# battery-module-60mm-side.net
KiCad netlist of a schematic drawn in Altium Designer
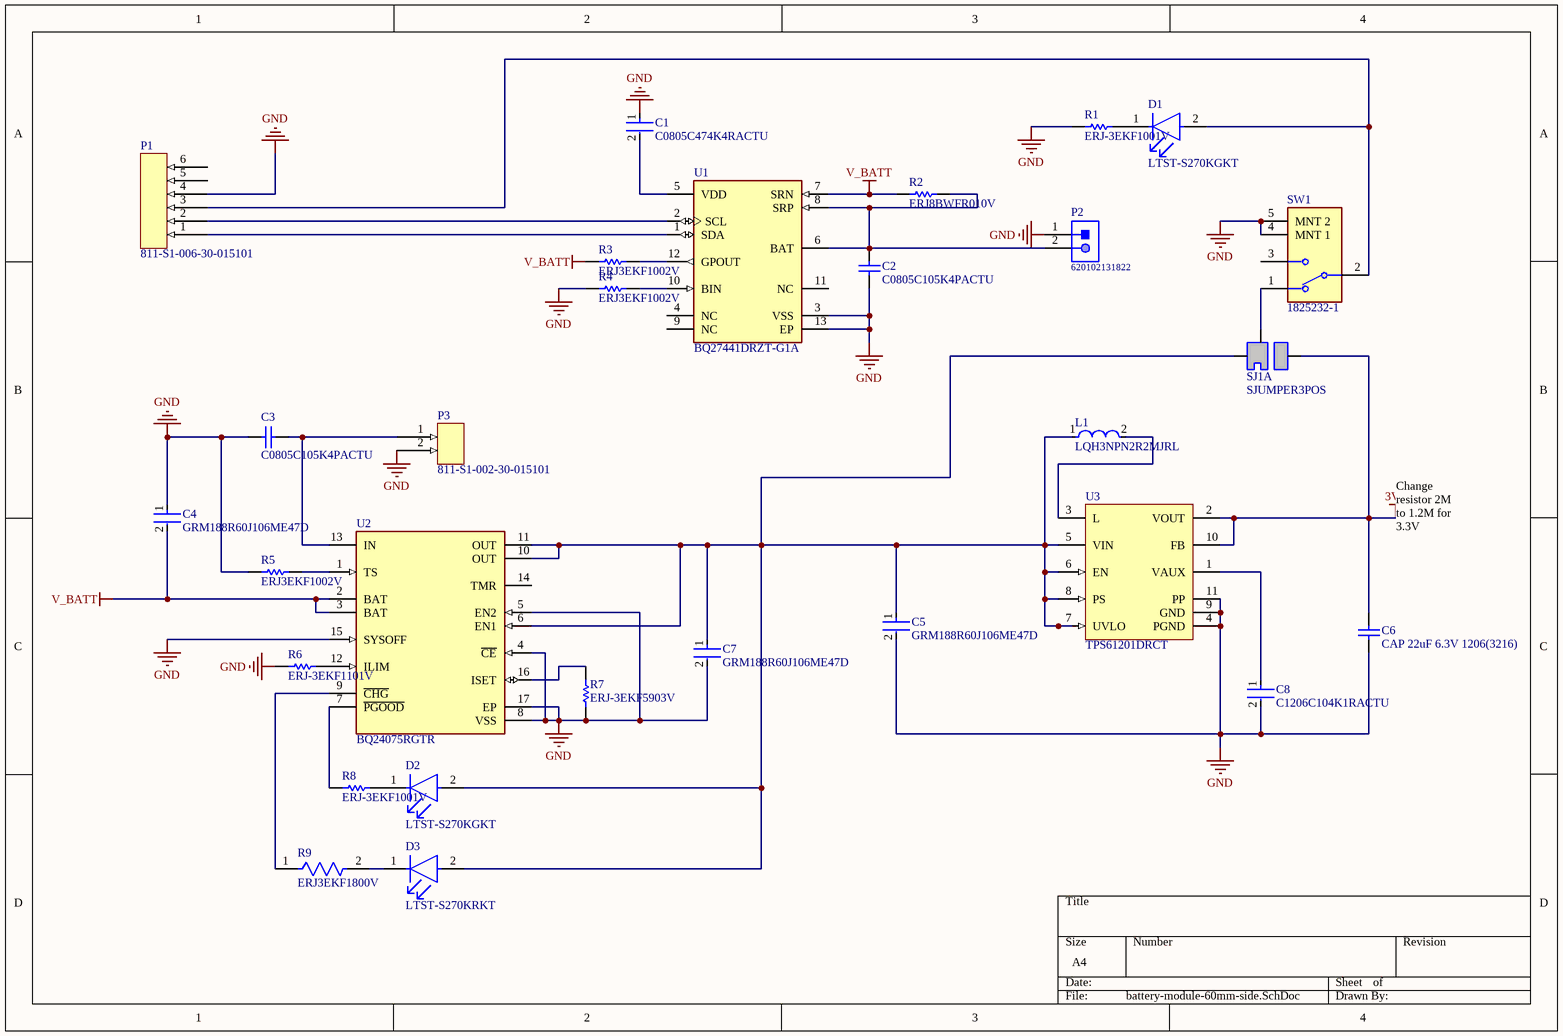
[diagram p0: battery-module-60mm-side.SchDoc]

(export (version "E")
  (design (tool "Eeschema 10.0.6"))
  (components
    (comp (ref "C1")
      (value "C0805C474K4RACTU")
      (footprint "FP-C0805C-DN-MFG")
      (description "CAP CER 0.47UF 16V 10% X7R 0805")
      (fields
        (field (name "OCTOPART") "https://octopart.com/c0805c474k4ractu-kemet-107561")
        (field (name "MANUFACTURER") "KEMET")
      )
      (libsource (lib "Altium Content Vault") (part "b4654b650e69147ec39a6b967a45e02"))
    )
    (comp (ref "C2")
      (value "C0805C105K4PACTU")
      (footprint "CAPC2013X145X50ML20T25")
      (fields (field (name "MANUFACTURER") "Kemet"))
      (libsource (lib "Altium Content Vault") (part "CAP"))
    )
    (comp (ref "C3")
      (value "C0805C105K4PACTU")
      (footprint "CAPC2013X145X50ML20T25")
      (fields (field (name "MANUFACTURER") "Kemet"))
      (libsource (lib "Altium Content Vault") (part "CAP"))
    )
    (comp (ref "C4")
      (value "GRM188R60J106ME47D")
      (footprint "FP-GRM188-0_1-e0_2_0_55-IPC_A")
      (description "Chip Multilayer Ceramic Capacitors for General Purpose, 0603, 10uF, X5R, 15%, 20%, 6.3V")
      (fields (field (name "VOLTAGE") "6.3V") (field (name "TOLERANCE") "20%"))
      (libsource (lib "Altium Content Vault") (part "02cd4be3c70576c341d710602a673aa"))
    )
    (comp (ref "C5")
      (value "GRM188R60J106ME47D")
      (footprint "FP-GRM188-0_1-e0_2_0_55-IPC_A")
      (description "Chip Multilayer Ceramic Capacitors for General Purpose, 0603, 10uF, X5R, 15%, 20%, 6.3V")
      (fields (field (name "VOLTAGE") "6.3V") (field (name "TOLERANCE") "20%"))
      (libsource (lib "Altium Content Vault") (part "02cd4be3c70576c341d710602a673aa"))
    )
    (comp (ref "C6")
      (value "CAP 22uF 6.3V 1206(3216)")
      (footprint "CAPC1206(3216)190_L")
      (description "CAP 22uF 6.3V ±20% 1206 (3216 Metric) Thickness 1.9mm SMD")
      (fields (field (name "TOLERANCE") "Â±20%"))
      (libsource (lib "Altium Content Vault") (part "CAP"))
    )
    (comp (ref "C7")
      (value "GRM188R60J106ME47D")
      (footprint "FP-GRM188-0_1-e0_2_0_55-IPC_A")
      (description "Chip Multilayer Ceramic Capacitors for General Purpose, 0603, 10uF, X5R, 15%, 20%, 6.3V")
      (fields (field (name "VOLTAGE") "6.3V") (field (name "TOLERANCE") "20%"))
      (libsource (lib "Altium Content Vault") (part "02cd4be3c70576c341d710602a673aa"))
    )
    (comp (ref "C8")
      (value "C1206C104K1RACTU")
      (footprint "FP-C1206C-EB-MFG")
      (description "CAP CER 0.1UF 100V X7R 1206")
      (fields
        (field (name "TOLERANCE") "0.1")
        (field (name "OCTOPART") "https://octopart.com/c1206c104k1ractu-kemet-89521")
      )
      (libsource (lib "Altium Content Vault") (part "b4654b650e69147ec39a6b967a45e02"))
    )
    (comp (ref "D1")
      (value "LTST-S270KGKT")
      (footprint "FP-LTST-S270KGKT-MFG")
      (description "LED GREEN CLEAR CHIP SMD R/A")
      (libsource (lib "Altium Content Vault") (part "8706943c75ba83719d021d2fdc84c58"))
    )
    (comp (ref "D2")
      (value "LTST-S270KGKT")
      (footprint "FP-LTST-S270KGKT-MFG")
      (description "LED GREEN CLEAR CHIP SMD R/A")
      (libsource (lib "Altium Content Vault") (part "8706943c75ba83719d021d2fdc84c58"))
    )
    (comp (ref "D3")
      (value "LTST-S270KRKT")
      (footprint "FP-LTST-S270KRKT-MFG")
      (description "LED RED CLEAR CHIP SMD R/A")
      (libsource (lib "Altium Content Vault") (part "8706943c75ba83719d021d2fdc84c58"))
    )
    (comp (ref "L1")
      (value "LQH3NPN2R2MJRL")
      (footprint "FP-LQH3NPN_JR-MFG")
      (description "Wire Wound Ferrite Inductor for Power Lines 2.2μH ±20% 0.0816Ω 2200mA 1212")
      (fields (field (name "TOLERANCE") "20%"))
      (libsource (lib "Altium Content Vault") (part "725321dda6339637d4d059423bc1c3c"))
    )
    (comp (ref "P1")
      (value "811-S1-006-30-015101")
      (footprint "New footprint 1")
      (description "Conn Spring Piston 6POS SMD")
      (libsource (lib "EPFL") (part "New symbol 1"))
    )
    (comp (ref "P2")
      (value "620102131822")
      (footprint "620102131822")
      (description "Male Shrouded Header WR-WTB, SMT, Right Angled, pitch 2 mm, 1 x 2 position")
      (fields (field (name "MANUFACTURER") "Wurth Elektronik") (field (name "PUBLISHER") "WurthElektronik"))
      (libsource (lib "Altium Content Vault") (part "WE-CN-1P-M-R2"))
    )
    (comp (ref "P3")
      (value "811-S1-002-30-015101")
      (footprint "811-S1-002-30-015101-Footprint-1")
      (description "Conn Spring Loaded Connector HDR 2 POS 2.54mm Solder ST SMD T/R")
      (libsource (lib "EPFL") (part "811-S1-002-30-015101-Symbol-1"))
    )
    (comp (ref "R1")
      (value "ERJ-3EKF1001V")
      (footprint "RESC1608X55X30ML15T15")
      (fields (field (name "MANUFACTURER") "Panasonic"))
      (libsource (lib "Altium Content Vault") (part "RES"))
    )
    (comp (ref "R2")
      (value "ERJ8BWFR010V")
      (footprint "RESC3216X70X50NL05T20")
      (fields (field (name "MANUFACTURER") "Panasonic"))
      (libsource (lib "Altium Content Vault") (part "RES"))
    )
    (comp (ref "R3")
      (value "ERJ3EKF1002V")
      (footprint "RESC1609X55X30ML15T15")
      (description "Chip Resistor, 10 KOhm, +/- 1%, 0.1 W, -55 to 155 degC, 0603 (1608 Metric), RoHS, Tape and Reel")
      (fields (field (name "TOLERANCE") "1%") (field (name "MANUFACTURER") "Panasonic"))
      (libsource (lib "Altium Content Vault") (part "RES-2"))
    )
    (comp (ref "R4")
      (value "ERJ3EKF1002V")
      (footprint "RESC1609X55X30ML15T15")
      (description "Chip Resistor, 10 KOhm, +/- 1%, 0.1 W, -55 to 155 degC, 0603 (1608 Metric), RoHS, Tape and Reel")
      (fields (field (name "TOLERANCE") "1%") (field (name "MANUFACTURER") "Panasonic"))
      (libsource (lib "Altium Content Vault") (part "RES-2"))
    )
    (comp (ref "R5")
      (value "ERJ3EKF1002V")
      (footprint "RESC1609X55X30ML15T15")
      (description "Chip Resistor, 10 KOhm, +/- 1%, 0.1 W, -55 to 155 degC, 0603 (1608 Metric), RoHS, Tape and Reel")
      (fields (field (name "TOLERANCE") "1%") (field (name "MANUFACTURER") "Panasonic"))
      (libsource (lib "Altium Content Vault") (part "RES-2"))
    )
    (comp (ref "R6")
      (value "ERJ-3EKF1101V")
      (footprint "RESC1608X55X30ML15T15")
      (fields (field (name "MANUFACTURER") "Panasonic"))
      (libsource (lib "Altium Content Vault") (part "RES"))
    )
    (comp (ref "R7")
      (value "ERJ-3EKF5903V")
      (footprint "RESC1608X55X30ML15T15")
      (fields (field (name "MANUFACTURER") "Panasonic"))
      (libsource (lib "Altium Content Vault") (part "RES"))
    )
    (comp (ref "R8")
      (value "ERJ-3EKF1001V")
      (footprint "RESC1608X55X30ML15T15")
      (fields (field (name "MANUFACTURER") "Panasonic"))
      (libsource (lib "Altium Content Vault") (part "RES"))
    )
    (comp (ref "R9")
      (value "ERJ3EKF1800V")
      (footprint "FP-ERJ3EK-MFG")
      (description "RES SMD 180 OHM 1% 1/10W 0603")
      (fields
        (field (name "OCTOPART") "https://octopart.com/erj-3ekf1800v-panasonic-55421532")
        (field (name "MANUFACTURER") "Panasonic")
      )
      (libsource (lib "Altium Content Vault") (part "1029c3af85768c4190bb7ad29bc67b5"))
    )
    (comp (ref "SJ1")
      (value "SJUMPER3POS")
      (footprint "SJUMPER3POS-Footprint-1")
      (description "3 pins solder jumper")
      (libsource (lib "EPFL") (part "SJUMPER3POS-Symbol-1"))
    )
    (comp (ref "SW1")
      (value "1825232-1")
      (footprint "FP-1825232-1-MFG")
      (description "SWITCH SLIDE SPDT 200MA 30V")
      (fields
        (field (name "OCTOPART") "https://octopart.com/1825232-1-te+connectivity-45209882")
        (field (name "MANUFACTURER") "TE Connectivity")
      )
      (libsource (lib "Altium Content Vault") (part "b81b21e7de6c425a317152e587b8097"))
    )
    (comp (ref "U1")
      (value "BQ27441DRZT-G1A")
      (footprint "FP-DRZ0012A-MFG")
      (description "IC BATT FUEL GAUGE LICOO2 12SON")
      (fields
        (field (name "OCTOPART") "https://octopart.com/bq27441drzt-g1a-texas+instruments-30555831")
        (field (name "MANUFACTURER") "Texas Instruments")
      )
      (libsource (lib "Altium Content Vault") (part "c803e035ce0891ae19034f27297cdee"))
    )
    (comp (ref "U2")
      (value "BQ24075RGTR")
      (footprint "FP-RGT0016C-IPC_A")
      (description "IC LI-ION CHARGE MGMT 16-QFN")
      (libsource (lib "Altium Content Vault") (part "273aa663c5dc25a29e76a3da5be16cc"))
    )
    (comp (ref "U3")
      (value "TPS61201DRCT")
      (footprint "DRC0010J_V")
      (fields (field (name "MANUFACTURER") "Texas Instruments"))
      (libsource (lib "Altium Content Vault") (part "TI-TPS61201DRC10-2400X1650TP"))
    )
  )
  (nets
    (net (code "1") (name "3V3") (class "Default")
      (node (ref "C6") (pin "2") (pinfunction "2_2") (pintype "passive"))
      (node (ref "SJ1") (pin "3") (pinfunction "3_3") (pintype "passive"))
      (node (ref "U3") (pin "10") (pinfunction "FB_10") (pintype "passive"))
      (node (ref "U3") (pin "2") (pinfunction "VOUT_2") (pintype "power_in"))
    )
    (net (code "2") (name "GND") (class "Default")
      (node (ref "C1") (pin "1") (pinfunction "1_1") (pintype "passive"))
      (node (ref "C2") (pin "1") (pinfunction "1_1") (pintype "passive"))
      (node (ref "C3") (pin "2") (pinfunction "2_2") (pintype "passive"))
      (node (ref "C4") (pin "1") (pinfunction "1_1") (pintype "passive"))
      (node (ref "C5") (pin "2") (pinfunction "2_2") (pintype "passive"))
      (node (ref "C6") (pin "1") (pinfunction "1_1") (pintype "passive"))
      (node (ref "C7") (pin "2") (pinfunction "2_2") (pintype "passive"))
      (node (ref "C8") (pin "2") (pinfunction "2_2") (pintype "passive"))
      (node (ref "P1") (pin "4") (pintype "input"))
      (node (ref "P2") (pin "1") (pinfunction "1_1") (pintype "passive"))
      (node (ref "P3") (pin "2") (pintype "input"))
      (node (ref "R1") (pin "1") (pinfunction "1_1") (pintype "passive"))
      (node (ref "R4") (pin "1") (pinfunction "1_1") (pintype "passive"))
      (node (ref "R5") (pin "1") (pinfunction "1_1") (pintype "passive"))
      (node (ref "R6") (pin "1") (pinfunction "1_1") (pintype "passive"))
      (node (ref "R7") (pin "1") (pinfunction "1_1") (pintype "passive"))
      (node (ref "SW1") (pin "4") (pinfunction "MNT_1_4") (pintype "passive"))
      (node (ref "SW1") (pin "5") (pinfunction "MNT_2_5") (pintype "passive"))
      (node (ref "U1") (pin "13") (pinfunction "EP_13") (pintype "power_in"))
      (node (ref "U1") (pin "3") (pinfunction "VSS_3") (pintype "power_in"))
      (node (ref "U2") (pin "15") (pinfunction "SYSOFF_15") (pintype "input"))
      (node (ref "U2") (pin "17") (pinfunction "EP_17") (pintype "power_in"))
      (node (ref "U2") (pin "4") (pinfunction "~{CE}_4") (pintype "input"))
      (node (ref "U2") (pin "5") (pinfunction "EN2_5") (pintype "input"))
      (node (ref "U2") (pin "8") (pinfunction "VSS_8") (pintype "power_in"))
      (node (ref "U3") (pin "11") (pinfunction "PP_11") (pintype "power_in"))
      (node (ref "U3") (pin "4") (pinfunction "PGND_4") (pintype "power_in"))
      (node (ref "U3") (pin "9") (pinfunction "GND_9") (pintype "power_in"))
    )
    (net (code "3") (name "Net-(D1-A)") (class "Default")
      (node (ref "D1") (pin "2") (pinfunction "A_2") (pintype "passive"))
      (node (ref "P1") (pin "3") (pintype "input"))
      (node (ref "SW1") (pin "2") (pinfunction "2_2") (pintype "passive"))
    )
    (net (code "4") (name "Net-(D1-C)") (class "Default")
      (node (ref "D1") (pin "1") (pinfunction "C_1") (pintype "passive"))
      (node (ref "R1") (pin "2") (pinfunction "2_2") (pintype "passive"))
    )
    (net (code "5") (name "Net-(D2-A)") (class "Default")
      (node (ref "C5") (pin "1") (pinfunction "1_1") (pintype "passive"))
      (node (ref "C7") (pin "1") (pinfunction "1_1") (pintype "passive"))
      (node (ref "D2") (pin "2") (pinfunction "A_2") (pintype "passive"))
      (node (ref "D3") (pin "2") (pinfunction "A_2") (pintype "passive"))
      (node (ref "L1") (pin "1") (pinfunction "1_1") (pintype "passive"))
      (node (ref "SJ1") (pin "1") (pinfunction "1_1") (pintype "passive"))
      (node (ref "U2") (pin "10") (pinfunction "OUT_10") (pintype "power_in"))
      (node (ref "U2") (pin "11") (pinfunction "OUT_11") (pintype "power_in"))
      (node (ref "U2") (pin "6") (pinfunction "EN1_6") (pintype "input"))
      (node (ref "U3") (pin "5") (pinfunction "VIN_5") (pintype "power_in"))
      (node (ref "U3") (pin "6") (pinfunction "EN_6") (pintype "input"))
      (node (ref "U3") (pin "7") (pinfunction "UVLO_7") (pintype "input"))
      (node (ref "U3") (pin "8") (pinfunction "PS_8") (pintype "input"))
    )
    (net (code "6") (name "Net-(D2-C)") (class "Default")
      (node (ref "D2") (pin "1") (pinfunction "C_1") (pintype "passive"))
      (node (ref "R8") (pin "2") (pinfunction "2_2") (pintype "passive"))
    )
    (net (code "7") (name "Net-(D3-C)") (class "Default")
      (node (ref "D3") (pin "1") (pinfunction "C_1") (pintype "passive"))
      (node (ref "R9") (pin "2") (pinfunction "2_2") (pintype "passive"))
    )
    (net (code "8") (name "Net-(SJ1-Pad2)") (class "Default")
      (node (ref "SJ1") (pin "2") (pinfunction "2_2") (pintype "passive"))
      (node (ref "SW1") (pin "1") (pinfunction "1_1") (pintype "passive"))
    )
    (net (code "9") (name "Net-(U1-BAT)") (class "Default")
      (node (ref "C2") (pin "2") (pinfunction "2_2") (pintype "passive"))
      (node (ref "P2") (pin "2") (pinfunction "2_2") (pintype "passive"))
      (node (ref "R2") (pin "2") (pinfunction "2_2") (pintype "passive"))
      (node (ref "U1") (pin "6") (pinfunction "BAT_6") (pintype "power_in"))
      (node (ref "U1") (pin "8") (pinfunction "SRP_8") (pintype "input"))
    )
    (net (code "10") (name "Net-(U1-BIN)") (class "Default")
      (node (ref "R4") (pin "2") (pinfunction "2_2") (pintype "passive"))
      (node (ref "U1") (pin "10") (pinfunction "BIN_10") (pintype "input"))
    )
    (net (code "11") (name "Net-(U1-GPOUT)") (class "Default")
      (node (ref "R3") (pin "2") (pinfunction "2_2") (pintype "passive"))
      (node (ref "U1") (pin "12") (pinfunction "GPOUT_12") (pintype "output"))
    )
    (net (code "12") (name "Net-(U1-SCL)") (class "Default")
      (node (ref "P1") (pin "2") (pintype "input"))
      (node (ref "U1") (pin "2") (pinfunction "SCL_2") (pintype "bidirectional"))
    )
    (net (code "13") (name "Net-(U1-SDA)") (class "Default")
      (node (ref "P1") (pin "1") (pintype "input"))
      (node (ref "U1") (pin "1") (pinfunction "SDA_1") (pintype "bidirectional"))
    )
    (net (code "14") (name "Net-(U1-VDD)") (class "Default")
      (node (ref "C1") (pin "2") (pinfunction "2_2") (pintype "passive"))
      (node (ref "U1") (pin "5") (pinfunction "VDD_5") (pintype "power_in"))
    )
    (net (code "15") (name "Net-(U2-ILIM)") (class "Default")
      (node (ref "R6") (pin "2") (pinfunction "2_2") (pintype "passive"))
      (node (ref "U2") (pin "12") (pinfunction "ILIM_12") (pintype "input"))
    )
    (net (code "16") (name "Net-(U2-IN)") (class "Default")
      (node (ref "C3") (pin "1") (pinfunction "1_1") (pintype "passive"))
      (node (ref "P3") (pin "1") (pintype "input"))
      (node (ref "U2") (pin "13") (pinfunction "IN_13") (pintype "power_in"))
    )
    (net (code "17") (name "Net-(U2-ISET)") (class "Default")
      (node (ref "R7") (pin "2") (pinfunction "2_2") (pintype "passive"))
      (node (ref "U2") (pin "16") (pinfunction "ISET_16") (pintype "bidirectional"))
    )
    (net (code "18") (name "Net-(U2-TS)") (class "Default")
      (node (ref "R5") (pin "2") (pinfunction "2_2") (pintype "passive"))
      (node (ref "U2") (pin "1") (pinfunction "TS_1") (pintype "input"))
    )
    (net (code "19") (name "Net-(U2-~{CHG})") (class "Default")
      (node (ref "R9") (pin "1") (pinfunction "1_1") (pintype "passive"))
      (node (ref "U2") (pin "9") (pinfunction "~{CHG}_9") (pintype "tri_state"))
    )
    (net (code "20") (name "Net-(U2-~{PGOOD})") (class "Default")
      (node (ref "R8") (pin "1") (pinfunction "1_1") (pintype "passive"))
      (node (ref "U2") (pin "7") (pinfunction "~{PGOOD}_7") (pintype "tri_state"))
    )
    (net (code "21") (name "Net-(U3-L)") (class "Default")
      (node (ref "L1") (pin "2") (pinfunction "2_2") (pintype "passive"))
      (node (ref "U3") (pin "3") (pinfunction "L_3") (pintype "power_in"))
    )
    (net (code "22") (name "Net-(U3-VAUX)") (class "Default")
      (node (ref "C8") (pin "1") (pinfunction "1_1") (pintype "passive"))
      (node (ref "U3") (pin "1") (pinfunction "VAUX_1") (pintype "power_in"))
    )
    (net (code "23") (name "V_BATT") (class "Default")
      (node (ref "C4") (pin "2") (pinfunction "2_2") (pintype "passive"))
      (node (ref "R2") (pin "1") (pinfunction "1_1") (pintype "passive"))
      (node (ref "R3") (pin "1") (pinfunction "1_1") (pintype "passive"))
      (node (ref "U1") (pin "7") (pinfunction "SRN_7") (pintype "input"))
      (node (ref "U2") (pin "2") (pinfunction "BAT_2") (pintype "power_in"))
      (node (ref "U2") (pin "3") (pinfunction "BAT_3") (pintype "power_in"))
    )
    (net (code "24") (name "unconnected-(P1-Pad5)") (class "Default")
      (node (ref "P1") (pin "5") (pintype "input"))
    )
    (net (code "25") (name "unconnected-(P1-Pad6)") (class "Default")
      (node (ref "P1") (pin "6") (pintype "input"))
    )
    (net (code "26") (name "unconnected-(SW1-Pad3)") (class "Default")
      (node (ref "SW1") (pin "3") (pinfunction "3_3") (pintype "passive"))
    )
    (net (code "27") (name "unconnected-(U1-NC-Pad4)") (class "Default")
      (node (ref "U1") (pin "4") (pinfunction "NC_4") (pintype "passive"))
    )
    (net (code "28") (name "unconnected-(U1-NC-Pad9)") (class "Default")
      (node (ref "U1") (pin "9") (pinfunction "NC_9") (pintype "power_in"))
    )
    (net (code "29") (name "unconnected-(U1-NC-Pad11)") (class "Default")
      (node (ref "U1") (pin "11") (pinfunction "NC_11") (pintype "passive"))
    )
    (net (code "30") (name "unconnected-(U2-TMR-Pad14)") (class "Default")
      (node (ref "U2") (pin "14") (pinfunction "TMR_14") (pintype "passive"))
    )
  )
)
